# Nestling_2_1_EXB.net
KiCad netlist of a schematic drawn in Altium Designer
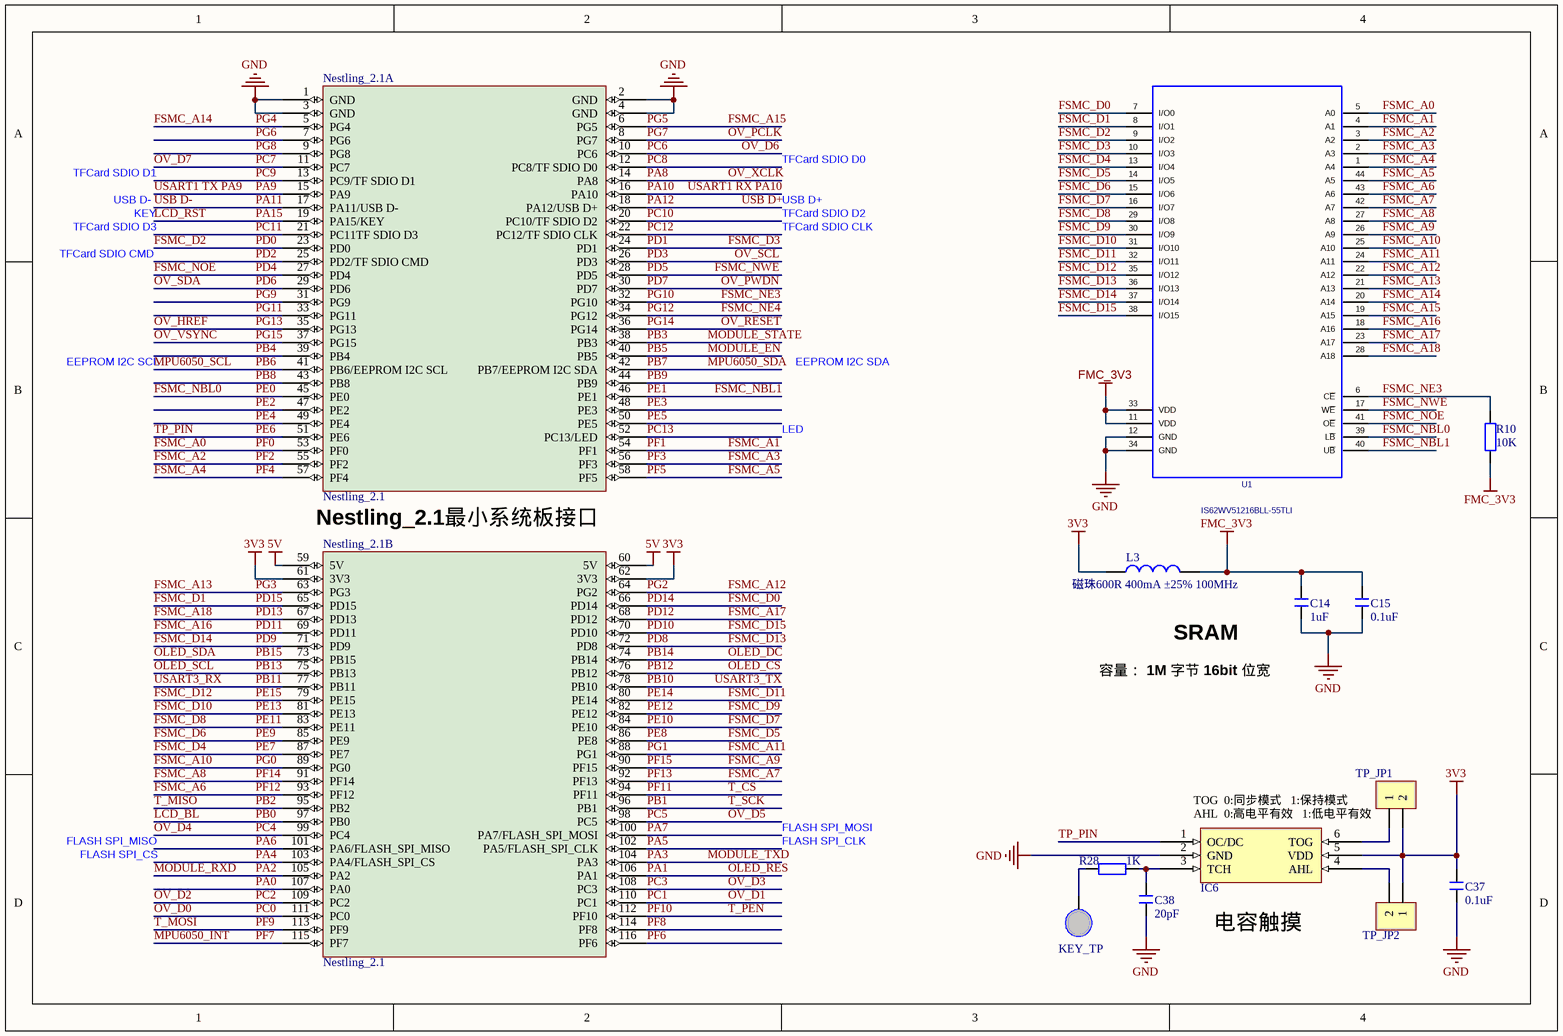
[diagram p0: Nestling_2.1_EXB.SchDoc]

(export (version "E")
  (design (tool "Eeschema 10.0.6"))
  (components
    (comp (ref "C14")
      (value "1uF")
      (footprint "C 0603_M")
      (description "无极性贴片电容")
      (fields (field (name "版权归属") "源创客"))
      (libsource (lib "altium-import") (part "root_1_C_"))
    )
    (comp (ref "C15")
      (value "0.1uF")
      (footprint "C 0603_M")
      (description "无极性贴片电容")
      (fields (field (name "版权归属") "源创客"))
      (libsource (lib "altium-import") (part "root_1_C_"))
    )
    (comp (ref "C37")
      (value "0.1uF")
      (footprint "C 0603_M")
      (description "无极性贴片电容")
      (fields (field (name "版权归属") "源创客"))
      (libsource (lib "altium-import") (part "root_1_C_"))
    )
    (comp (ref "C38")
      (value "20pF")
      (footprint "C 0603_M")
      (description "无极性贴片电容")
      (fields (field (name "版权归属") "源创客"))
      (libsource (lib "altium-import") (part "root_1_C_"))
    )
    (comp (ref "IC6")
      (value "RH6015C SOT23-6")
      (footprint "SOT23-6N")
      (description "贴片单通道电容式触摸感应控制开关IC")
      (libsource (lib "1.1   - IC芯片") (part "RH6015C"))
    )
    (comp (ref "KEY_TP")
      (value "TP_Pin")
      (footprint "TP_PIN_10*13mm")
      (libsource (lib "MyLib") (part "TP_Pin"))
    )
    (comp (ref "L3")
      (value "磁珠600R 400mA ±25% 100MHz")
      (footprint "L 0603")
      (description "小功率贴片电感")
      (fields (field (name "版权归属") "源创客"))
      (libsource (lib "altium-import") (part "root_0_L_"))
    )
    (comp (ref "Nestling_2.1")
      (value "Nestling_2.1")
      (footprint "Nestling_2.1")
      (libsource (lib "altium-import") (part "root_0_Nestling_2.1_"))
    )
    (comp (ref "R10")
      (value "10K")
      (footprint "R 0603_M")
      (description "Resistor")
      (libsource (lib "General") (part "RES"))
    )
    (comp (ref "R28")
      (value "1K")
      (footprint "R 0603_M")
      (description "Resistor")
      (libsource (lib "") (part "RES_1"))
    )
    (comp (ref "TP_JP1")
      (value "HDR-1X2")
      (footprint "HDR2.54-LI-2P")
      (description "2P接插件")
      (fields (field (name "版权归属") "源创客"))
      (libsource (lib "") (part "Header 2_1"))
    )
    (comp (ref "TP_JP2")
      (value "HDR-1X2")
      (footprint "HDR2.54-LI-2P")
      (description "2P接插件")
      (fields (field (name "版权归属") "源创客"))
      (libsource (lib "4.5   - 接插件-脚距2.54") (part "Header 2"))
    )
    (comp (ref "U1")
      (value "IS62WV51216BLL-55TLI")
      (footprint "TSOP44-0.8MM")
      (description "TSOP-II,2.5V - 3.6V, 512K x 16,55ns")
      (fields (field (name "TOLERANCE") "55ns"))
      (libsource (lib "altium-import") (part "root_0_IS62WV51216BLL-55TLI_"))
    )
  )
  (nets
    (net (code "1") (name "/FSMC_A0") (class "Default")
      (node (ref "Nestling_2.1") (pin "53") (pinfunction "PF0_53") (pintype "bidirectional"))
      (node (ref "U1") (pin "5") (pinfunction "A0_5") (pintype "passive"))
    )
    (net (code "2") (name "/FSMC_A1") (class "Default")
      (node (ref "Nestling_2.1") (pin "54") (pinfunction "PF1_54") (pintype "bidirectional"))
      (node (ref "U1") (pin "4") (pinfunction "A1_4") (pintype "passive"))
    )
    (net (code "3") (name "/FSMC_A2") (class "Default")
      (node (ref "Nestling_2.1") (pin "55") (pinfunction "PF2_55") (pintype "bidirectional"))
      (node (ref "U1") (pin "3") (pinfunction "A2_3") (pintype "passive"))
    )
    (net (code "4") (name "/FSMC_A3") (class "Default")
      (node (ref "Nestling_2.1") (pin "56") (pinfunction "PF3_56") (pintype "bidirectional"))
      (node (ref "U1") (pin "2") (pinfunction "A3_2") (pintype "passive"))
    )
    (net (code "5") (name "/FSMC_A4") (class "Default")
      (node (ref "Nestling_2.1") (pin "57") (pinfunction "PF4_57") (pintype "bidirectional"))
      (node (ref "U1") (pin "1") (pinfunction "A4_1") (pintype "passive"))
    )
    (net (code "6") (name "/FSMC_A5") (class "Default")
      (node (ref "Nestling_2.1") (pin "58") (pinfunction "PF5_58") (pintype "bidirectional"))
      (node (ref "U1") (pin "44") (pinfunction "A5_44") (pintype "passive"))
    )
    (net (code "7") (name "/FSMC_A6") (class "Default")
      (node (ref "Nestling_2.1") (pin "93") (pinfunction "PF12_93") (pintype "bidirectional"))
      (node (ref "U1") (pin "43") (pinfunction "A6_43") (pintype "passive"))
    )
    (net (code "8") (name "/FSMC_A7") (class "Default")
      (node (ref "Nestling_2.1") (pin "92") (pinfunction "PF13_92") (pintype "bidirectional"))
      (node (ref "U1") (pin "42") (pinfunction "A7_42") (pintype "passive"))
    )
    (net (code "9") (name "/FSMC_A8") (class "Default")
      (node (ref "Nestling_2.1") (pin "91") (pinfunction "PF14_91") (pintype "bidirectional"))
      (node (ref "U1") (pin "27") (pinfunction "A8_27") (pintype "passive"))
    )
    (net (code "10") (name "/FSMC_A9") (class "Default")
      (node (ref "Nestling_2.1") (pin "90") (pinfunction "PF15_90") (pintype "bidirectional"))
      (node (ref "U1") (pin "26") (pinfunction "A9_26") (pintype "passive"))
    )
    (net (code "11") (name "/FSMC_A10") (class "Default")
      (node (ref "Nestling_2.1") (pin "89") (pinfunction "PG0_89") (pintype "bidirectional"))
      (node (ref "U1") (pin "25") (pinfunction "A10_25") (pintype "passive"))
    )
    (net (code "12") (name "/FSMC_A11") (class "Default")
      (node (ref "Nestling_2.1") (pin "88") (pinfunction "PG1_88") (pintype "bidirectional"))
      (node (ref "U1") (pin "24") (pinfunction "A11_24") (pintype "passive"))
    )
    (net (code "13") (name "/FSMC_A12") (class "Default")
      (node (ref "Nestling_2.1") (pin "64") (pinfunction "PG2_64") (pintype "bidirectional"))
      (node (ref "U1") (pin "22") (pinfunction "A12_22") (pintype "passive"))
    )
    (net (code "14") (name "/FSMC_A13") (class "Default")
      (node (ref "Nestling_2.1") (pin "63") (pinfunction "PG3_63") (pintype "bidirectional"))
      (node (ref "U1") (pin "21") (pinfunction "A13_21") (pintype "passive"))
    )
    (net (code "15") (name "/FSMC_A14") (class "Default")
      (node (ref "Nestling_2.1") (pin "5") (pinfunction "PG4_5") (pintype "bidirectional"))
      (node (ref "U1") (pin "20") (pinfunction "A14_20") (pintype "passive"))
    )
    (net (code "16") (name "/FSMC_A15") (class "Default")
      (node (ref "Nestling_2.1") (pin "6") (pinfunction "PG5_6") (pintype "bidirectional"))
      (node (ref "U1") (pin "19") (pinfunction "A15_19") (pintype "passive"))
    )
    (net (code "17") (name "/FSMC_A16") (class "Default")
      (node (ref "Nestling_2.1") (pin "69") (pinfunction "PD11_69") (pintype "bidirectional"))
      (node (ref "U1") (pin "18") (pinfunction "A16_18") (pintype "passive"))
    )
    (net (code "18") (name "/FSMC_A17") (class "Default")
      (node (ref "Nestling_2.1") (pin "68") (pinfunction "PD12_68") (pintype "bidirectional"))
      (node (ref "U1") (pin "23") (pinfunction "A17_23") (pintype "passive"))
    )
    (net (code "19") (name "/FSMC_A18") (class "Default")
      (node (ref "Nestling_2.1") (pin "67") (pinfunction "PD13_67") (pintype "bidirectional"))
      (node (ref "U1") (pin "28") (pinfunction "A18_28") (pintype "passive"))
    )
    (net (code "20") (name "/FSMC_D0") (class "Default")
      (node (ref "Nestling_2.1") (pin "66") (pinfunction "PD14_66") (pintype "bidirectional"))
      (node (ref "U1") (pin "7") (pinfunction "I/O0_7") (pintype "passive"))
    )
    (net (code "21") (name "/FSMC_D1") (class "Default")
      (node (ref "Nestling_2.1") (pin "65") (pinfunction "PD15_65") (pintype "bidirectional"))
      (node (ref "U1") (pin "8") (pinfunction "I/O1_8") (pintype "passive"))
    )
    (net (code "22") (name "/FSMC_D2") (class "Default")
      (node (ref "Nestling_2.1") (pin "23") (pinfunction "PD0_23") (pintype "bidirectional"))
      (node (ref "U1") (pin "9") (pinfunction "I/O2_9") (pintype "passive"))
    )
    (net (code "23") (name "/FSMC_D3") (class "Default")
      (node (ref "Nestling_2.1") (pin "24") (pinfunction "PD1_24") (pintype "bidirectional"))
      (node (ref "U1") (pin "10") (pinfunction "I/O3_10") (pintype "passive"))
    )
    (net (code "24") (name "/FSMC_D4") (class "Default")
      (node (ref "Nestling_2.1") (pin "87") (pinfunction "PE7_87") (pintype "bidirectional"))
      (node (ref "U1") (pin "13") (pinfunction "I/O4_13") (pintype "passive"))
    )
    (net (code "25") (name "/FSMC_D5") (class "Default")
      (node (ref "Nestling_2.1") (pin "86") (pinfunction "PE8_86") (pintype "bidirectional"))
      (node (ref "U1") (pin "14") (pinfunction "I/O5_14") (pintype "passive"))
    )
    (net (code "26") (name "/FSMC_D6") (class "Default")
      (node (ref "Nestling_2.1") (pin "85") (pinfunction "PE9_85") (pintype "bidirectional"))
      (node (ref "U1") (pin "15") (pinfunction "I/O6_15") (pintype "passive"))
    )
    (net (code "27") (name "/FSMC_D7") (class "Default")
      (node (ref "Nestling_2.1") (pin "84") (pinfunction "PE10_84") (pintype "bidirectional"))
      (node (ref "U1") (pin "16") (pinfunction "I/O7_16") (pintype "passive"))
    )
    (net (code "28") (name "/FSMC_D8") (class "Default")
      (node (ref "Nestling_2.1") (pin "83") (pinfunction "PE11_83") (pintype "bidirectional"))
      (node (ref "U1") (pin "29") (pinfunction "I/O8_29") (pintype "passive"))
    )
    (net (code "29") (name "/FSMC_D9") (class "Default")
      (node (ref "Nestling_2.1") (pin "82") (pinfunction "PE12_82") (pintype "bidirectional"))
      (node (ref "U1") (pin "30") (pinfunction "I/O9_30") (pintype "passive"))
    )
    (net (code "30") (name "/FSMC_D10") (class "Default")
      (node (ref "Nestling_2.1") (pin "81") (pinfunction "PE13_81") (pintype "bidirectional"))
      (node (ref "U1") (pin "31") (pinfunction "I/O10_31") (pintype "passive"))
    )
    (net (code "31") (name "/FSMC_D11") (class "Default")
      (node (ref "Nestling_2.1") (pin "80") (pinfunction "PE14_80") (pintype "bidirectional"))
      (node (ref "U1") (pin "32") (pinfunction "I/O11_32") (pintype "passive"))
    )
    (net (code "32") (name "/FSMC_D12") (class "Default")
      (node (ref "Nestling_2.1") (pin "79") (pinfunction "PE15_79") (pintype "bidirectional"))
      (node (ref "U1") (pin "35") (pinfunction "I/O12_35") (pintype "passive"))
    )
    (net (code "33") (name "/FSMC_D13") (class "Default")
      (node (ref "Nestling_2.1") (pin "72") (pinfunction "PD8_72") (pintype "bidirectional"))
      (node (ref "U1") (pin "36") (pinfunction "I/O13_36") (pintype "passive"))
    )
    (net (code "34") (name "/FSMC_D14") (class "Default")
      (node (ref "Nestling_2.1") (pin "71") (pinfunction "PD9_71") (pintype "bidirectional"))
      (node (ref "U1") (pin "37") (pinfunction "I/O14_37") (pintype "passive"))
    )
    (net (code "35") (name "/FSMC_D15") (class "Default")
      (node (ref "Nestling_2.1") (pin "70") (pinfunction "PD10_70") (pintype "bidirectional"))
      (node (ref "U1") (pin "38") (pinfunction "I/O15_38") (pintype "passive"))
    )
    (net (code "36") (name "/FSMC_NBL0") (class "Default")
      (node (ref "Nestling_2.1") (pin "45") (pinfunction "PE0_45") (pintype "bidirectional"))
      (node (ref "U1") (pin "39") (pinfunction "L~{B}_39") (pintype "passive"))
    )
    (net (code "37") (name "/FSMC_NBL1") (class "Default")
      (node (ref "Nestling_2.1") (pin "46") (pinfunction "PE1_46") (pintype "bidirectional"))
      (node (ref "U1") (pin "40") (pinfunction "U~{B}_40") (pintype "passive"))
    )
    (net (code "38") (name "/FSMC_NE3") (class "Default")
      (node (ref "Nestling_2.1") (pin "32") (pinfunction "PG10_32") (pintype "bidirectional"))
      (node (ref "R10") (pin "1") (pinfunction "1_1") (pintype "passive"))
      (node (ref "U1") (pin "6") (pinfunction "C~{E}_6") (pintype "passive"))
    )
    (net (code "39") (name "/FSMC_NE4") (class "Default")
      (node (ref "Nestling_2.1") (pin "34") (pinfunction "PG12_34") (pintype "bidirectional"))
    )
    (net (code "40") (name "/FSMC_NOE") (class "Default")
      (node (ref "Nestling_2.1") (pin "27") (pinfunction "PD4_27") (pintype "bidirectional"))
      (node (ref "U1") (pin "41") (pinfunction "O~{E}_41") (pintype "passive"))
    )
    (net (code "41") (name "/FSMC_NWE") (class "Default")
      (node (ref "Nestling_2.1") (pin "28") (pinfunction "PD5_28") (pintype "bidirectional"))
      (node (ref "U1") (pin "17") (pinfunction "W~{E}_17") (pintype "passive"))
    )
    (net (code "42") (name "/LCD_BL") (class "Default")
      (node (ref "Nestling_2.1") (pin "97") (pinfunction "PB0_97") (pintype "bidirectional"))
    )
    (net (code "43") (name "/LCD_RST") (class "Default")
      (node (ref "Nestling_2.1") (pin "19") (pinfunction "PA15/KEY_19") (pintype "bidirectional"))
    )
    (net (code "44") (name "/MODULE_EN") (class "Default")
      (node (ref "Nestling_2.1") (pin "40") (pinfunction "PB5_40") (pintype "bidirectional"))
    )
    (net (code "45") (name "/MODULE_RXD") (class "Default")
      (node (ref "Nestling_2.1") (pin "105") (pinfunction "PA2_105") (pintype "bidirectional"))
    )
    (net (code "46") (name "/MODULE_STATE") (class "Default")
      (node (ref "Nestling_2.1") (pin "38") (pinfunction "PB3_38") (pintype "bidirectional"))
    )
    (net (code "47") (name "/MODULE_TXD") (class "Default")
      (node (ref "Nestling_2.1") (pin "104") (pinfunction "PA3_104") (pintype "bidirectional"))
    )
    (net (code "48") (name "/MPU6050_INT") (class "Default")
      (node (ref "Nestling_2.1") (pin "115") (pinfunction "PF7_115") (pintype "bidirectional"))
    )
    (net (code "49") (name "/MPU6050_SCL") (class "Default")
      (node (ref "Nestling_2.1") (pin "41") (pinfunction "PB6/EEPROM_I2C_SCL_41") (pintype "bidirectional"))
    )
    (net (code "50") (name "/MPU6050_SDA") (class "Default")
      (node (ref "Nestling_2.1") (pin "42") (pinfunction "PB7/EEPROM_I2C_SDA_42") (pintype "bidirectional"))
    )
    (net (code "51") (name "/OLED_CS") (class "Default")
      (node (ref "Nestling_2.1") (pin "76") (pinfunction "PB12_76") (pintype "bidirectional"))
    )
    (net (code "52") (name "/OLED_DC") (class "Default")
      (node (ref "Nestling_2.1") (pin "74") (pinfunction "PB14_74") (pintype "bidirectional"))
    )
    (net (code "53") (name "/OLED_RES") (class "Default")
      (node (ref "Nestling_2.1") (pin "106") (pinfunction "PA1_106") (pintype "bidirectional"))
    )
    (net (code "54") (name "/OLED_SCL") (class "Default")
      (node (ref "Nestling_2.1") (pin "75") (pinfunction "PB13_75") (pintype "bidirectional"))
    )
    (net (code "55") (name "/OLED_SDA") (class "Default")
      (node (ref "Nestling_2.1") (pin "73") (pinfunction "PB15_73") (pintype "bidirectional"))
    )
    (net (code "56") (name "/OV_D0") (class "Default")
      (node (ref "Nestling_2.1") (pin "111") (pinfunction "PC0_111") (pintype "bidirectional"))
    )
    (net (code "57") (name "/OV_D1") (class "Default")
      (node (ref "Nestling_2.1") (pin "110") (pinfunction "PC1_110") (pintype "bidirectional"))
    )
    (net (code "58") (name "/OV_D2") (class "Default")
      (node (ref "Nestling_2.1") (pin "109") (pinfunction "PC2_109") (pintype "bidirectional"))
    )
    (net (code "59") (name "/OV_D3") (class "Default")
      (node (ref "Nestling_2.1") (pin "108") (pinfunction "PC3_108") (pintype "bidirectional"))
    )
    (net (code "60") (name "/OV_D4") (class "Default")
      (node (ref "Nestling_2.1") (pin "99") (pinfunction "PC4_99") (pintype "bidirectional"))
    )
    (net (code "61") (name "/OV_D5") (class "Default")
      (node (ref "Nestling_2.1") (pin "98") (pinfunction "PC5_98") (pintype "bidirectional"))
    )
    (net (code "62") (name "/OV_D6") (class "Default")
      (node (ref "Nestling_2.1") (pin "10") (pinfunction "PC6_10") (pintype "bidirectional"))
    )
    (net (code "63") (name "/OV_D7") (class "Default")
      (node (ref "Nestling_2.1") (pin "11") (pinfunction "PC7_11") (pintype "bidirectional"))
    )
    (net (code "64") (name "/OV_HREF") (class "Default")
      (node (ref "Nestling_2.1") (pin "35") (pinfunction "PG13_35") (pintype "bidirectional"))
    )
    (net (code "65") (name "/OV_PCLK") (class "Default")
      (node (ref "Nestling_2.1") (pin "8") (pinfunction "PG7_8") (pintype "bidirectional"))
    )
    (net (code "66") (name "/OV_PWDN") (class "Default")
      (node (ref "Nestling_2.1") (pin "30") (pinfunction "PD7_30") (pintype "bidirectional"))
    )
    (net (code "67") (name "/OV_RESET") (class "Default")
      (node (ref "Nestling_2.1") (pin "36") (pinfunction "PG14_36") (pintype "bidirectional"))
    )
    (net (code "68") (name "/OV_SCL") (class "Default")
      (node (ref "Nestling_2.1") (pin "26") (pinfunction "PD3_26") (pintype "bidirectional"))
    )
    (net (code "69") (name "/OV_SDA") (class "Default")
      (node (ref "Nestling_2.1") (pin "29") (pinfunction "PD6_29") (pintype "bidirectional"))
    )
    (net (code "70") (name "/OV_VSYNC") (class "Default")
      (node (ref "Nestling_2.1") (pin "37") (pinfunction "PG15_37") (pintype "bidirectional"))
    )
    (net (code "71") (name "/OV_XCLK") (class "Default")
      (node (ref "Nestling_2.1") (pin "14") (pinfunction "PA8_14") (pintype "bidirectional"))
    )
    (net (code "72") (name "/PA0") (class "Default")
      (node (ref "Nestling_2.1") (pin "107") (pinfunction "PA0_107") (pintype "bidirectional"))
    )
    (net (code "73") (name "/PA4") (class "Default")
      (node (ref "Nestling_2.1") (pin "103") (pinfunction "PA4/FLASH_SPI_CS_103") (pintype "bidirectional"))
    )
    (net (code "74") (name "/PA5") (class "Default")
      (node (ref "Nestling_2.1") (pin "102") (pinfunction "PA5/FLASH_SPI_CLK_102") (pintype "bidirectional"))
    )
    (net (code "75") (name "/PA6") (class "Default")
      (node (ref "Nestling_2.1") (pin "101") (pinfunction "PA6/FLASH_SPI_MISO_101") (pintype "bidirectional"))
    )
    (net (code "76") (name "/PA7") (class "Default")
      (node (ref "Nestling_2.1") (pin "100") (pinfunction "PA7/FLASH_SPI_MOSI_100") (pintype "bidirectional"))
    )
    (net (code "77") (name "/PA9") (class "Default")
      (node (ref "Nestling_2.1") (pin "15") (pinfunction "PA9_15") (pintype "bidirectional"))
    )
    (net (code "78") (name "/PA10") (class "Default")
      (node (ref "Nestling_2.1") (pin "16") (pinfunction "PA10_16") (pintype "bidirectional"))
    )
    (net (code "79") (name "/PA11") (class "Default")
      (node (ref "Nestling_2.1") (pin "17") (pinfunction "PA11/USB_D-_17") (pintype "bidirectional"))
    )
    (net (code "80") (name "/PA12") (class "Default")
      (node (ref "Nestling_2.1") (pin "18") (pinfunction "PA12/USB_D+_18") (pintype "bidirectional"))
    )
    (net (code "81") (name "/PB1") (class "Default")
      (node (ref "Nestling_2.1") (pin "96") (pinfunction "PB1_96") (pintype "bidirectional"))
    )
    (net (code "82") (name "/PB2") (class "Default")
      (node (ref "Nestling_2.1") (pin "95") (pinfunction "PB2_95") (pintype "bidirectional"))
    )
    (net (code "83") (name "/PB4") (class "Default")
      (node (ref "Nestling_2.1") (pin "39") (pinfunction "PB4_39") (pintype "bidirectional"))
    )
    (net (code "84") (name "/PB8") (class "Default")
      (node (ref "Nestling_2.1") (pin "43") (pinfunction "PB8_43") (pintype "bidirectional"))
    )
    (net (code "85") (name "/PB9") (class "Default")
      (node (ref "Nestling_2.1") (pin "44") (pinfunction "PB9_44") (pintype "bidirectional"))
    )
    (net (code "86") (name "/PB10") (class "Default")
      (node (ref "Nestling_2.1") (pin "78") (pinfunction "PB10_78") (pintype "bidirectional"))
    )
    (net (code "87") (name "/PB11") (class "Default")
      (node (ref "Nestling_2.1") (pin "77") (pinfunction "PB11_77") (pintype "bidirectional"))
    )
    (net (code "88") (name "/PC8") (class "Default")
      (node (ref "Nestling_2.1") (pin "12") (pinfunction "PC8/TF_SDIO_D0_12") (pintype "bidirectional"))
    )
    (net (code "89") (name "/PC9") (class "Default")
      (node (ref "Nestling_2.1") (pin "13") (pinfunction "PC9/TF_SDIO_D1_13") (pintype "bidirectional"))
    )
    (net (code "90") (name "/PC10") (class "Default")
      (node (ref "Nestling_2.1") (pin "20") (pinfunction "PC10/TF_SDIO_D2_20") (pintype "bidirectional"))
    )
    (net (code "91") (name "/PC11") (class "Default")
      (node (ref "Nestling_2.1") (pin "21") (pinfunction "PC11TF_SDIO_D3_21") (pintype "bidirectional"))
    )
    (net (code "92") (name "/PC12") (class "Default")
      (node (ref "Nestling_2.1") (pin "22") (pinfunction "PC12/TF_SDIO_CLK_22") (pintype "bidirectional"))
    )
    (net (code "93") (name "/PC13") (class "Default")
      (node (ref "Nestling_2.1") (pin "52") (pinfunction "PC13/LED_52") (pintype "bidirectional"))
    )
    (net (code "94") (name "/PD2") (class "Default")
      (node (ref "Nestling_2.1") (pin "25") (pinfunction "PD2/TF_SDIO_CMD_25") (pintype "bidirectional"))
    )
    (net (code "95") (name "/PE2") (class "Default")
      (node (ref "Nestling_2.1") (pin "47") (pinfunction "PE2_47") (pintype "bidirectional"))
    )
    (net (code "96") (name "/PE3") (class "Default")
      (node (ref "Nestling_2.1") (pin "48") (pinfunction "PE3_48") (pintype "bidirectional"))
    )
    (net (code "97") (name "/PE4") (class "Default")
      (node (ref "Nestling_2.1") (pin "49") (pinfunction "PE4_49") (pintype "bidirectional"))
    )
    (net (code "98") (name "/PE5") (class "Default")
      (node (ref "Nestling_2.1") (pin "50") (pinfunction "PE5_50") (pintype "bidirectional"))
    )
    (net (code "99") (name "/PE6") (class "Default")
      (node (ref "IC6") (pin "1") (pinfunction "OC/DC_1") (pintype "input"))
      (node (ref "Nestling_2.1") (pin "51") (pinfunction "PE6_51") (pintype "bidirectional"))
    )
    (net (code "100") (name "/PF6") (class "Default")
      (node (ref "Nestling_2.1") (pin "116") (pinfunction "PF6_116") (pintype "bidirectional"))
    )
    (net (code "101") (name "/PF8") (class "Default")
      (node (ref "Nestling_2.1") (pin "114") (pinfunction "PF8_114") (pintype "bidirectional"))
    )
    (net (code "102") (name "/PF9") (class "Default")
      (node (ref "Nestling_2.1") (pin "113") (pinfunction "PF9_113") (pintype "bidirectional"))
    )
    (net (code "103") (name "/PF10") (class "Default")
      (node (ref "Nestling_2.1") (pin "112") (pinfunction "PF10_112") (pintype "bidirectional"))
    )
    (net (code "104") (name "/PF11") (class "Default")
      (node (ref "Nestling_2.1") (pin "94") (pinfunction "PF11_94") (pintype "bidirectional"))
    )
    (net (code "105") (name "/PG6") (class "Default")
      (node (ref "Nestling_2.1") (pin "7") (pinfunction "PG6_7") (pintype "bidirectional"))
    )
    (net (code "106") (name "/PG8") (class "Default")
      (node (ref "Nestling_2.1") (pin "9") (pinfunction "PG8_9") (pintype "bidirectional"))
    )
    (net (code "107") (name "/PG9") (class "Default")
      (node (ref "Nestling_2.1") (pin "31") (pinfunction "PG9_31") (pintype "bidirectional"))
    )
    (net (code "108") (name "/PG11") (class "Default")
      (node (ref "Nestling_2.1") (pin "33") (pinfunction "PG11_33") (pintype "bidirectional"))
    )
    (net (code "109") (name "3V3") (class "Default")
      (node (ref "C37") (pin "2") (pinfunction "2_2") (pintype "passive"))
      (node (ref "IC6") (pin "5") (pinfunction "VDD_5") (pintype "input"))
      (node (ref "L3") (pin "1") (pinfunction "1_1") (pintype "passive"))
      (node (ref "Nestling_2.1") (pin "61") (pinfunction "3V3_61") (pintype "bidirectional"))
      (node (ref "Nestling_2.1") (pin "62") (pinfunction "3V3_62") (pintype "bidirectional"))
      (node (ref "TP_JP1") (pin "2") (pinfunction "2_2") (pintype "passive"))
      (node (ref "TP_JP2") (pin "1") (pinfunction "1_1") (pintype "passive"))
    )
    (net (code "110") (name "5V") (class "Default")
      (node (ref "Nestling_2.1") (pin "59") (pinfunction "5V_59") (pintype "bidirectional"))
      (node (ref "Nestling_2.1") (pin "60") (pinfunction "5V_60") (pintype "bidirectional"))
    )
    (net (code "111") (name "FMC_3V3") (class "Default")
      (node (ref "C14") (pin "2") (pinfunction "2_2") (pintype "passive"))
      (node (ref "C15") (pin "2") (pinfunction "2_2") (pintype "passive"))
      (node (ref "L3") (pin "2") (pinfunction "2_2") (pintype "passive"))
      (node (ref "R10") (pin "2") (pinfunction "2_2") (pintype "passive"))
      (node (ref "U1") (pin "11") (pinfunction "VDD_11") (pintype "passive"))
      (node (ref "U1") (pin "33") (pinfunction "VDD_33") (pintype "passive"))
    )
    (net (code "112") (name "GND") (class "Default")
      (node (ref "C14") (pin "1") (pinfunction "1_1") (pintype "passive"))
      (node (ref "C15") (pin "1") (pinfunction "1_1") (pintype "passive"))
      (node (ref "C37") (pin "1") (pinfunction "1_1") (pintype "passive"))
      (node (ref "C38") (pin "1") (pinfunction "1_1") (pintype "passive"))
      (node (ref "IC6") (pin "2") (pinfunction "GND_2") (pintype "input"))
      (node (ref "Nestling_2.1") (pin "1") (pinfunction "GND_1") (pintype "bidirectional"))
      (node (ref "Nestling_2.1") (pin "2") (pinfunction "GND_2") (pintype "bidirectional"))
      (node (ref "Nestling_2.1") (pin "3") (pinfunction "GND_3") (pintype "bidirectional"))
      (node (ref "Nestling_2.1") (pin "4") (pinfunction "GND_4") (pintype "bidirectional"))
      (node (ref "U1") (pin "12") (pinfunction "GND_12") (pintype "passive"))
      (node (ref "U1") (pin "34") (pinfunction "GND_34") (pintype "passive"))
    )
    (net (code "113") (name "Net-(IC6-AHL)") (class "Default")
      (node (ref "IC6") (pin "4") (pinfunction "AHL_4") (pintype "input"))
      (node (ref "TP_JP2") (pin "2") (pinfunction "2_2") (pintype "passive"))
    )
    (net (code "114") (name "Net-(IC6-TCH)") (class "Default")
      (node (ref "C38") (pin "2") (pinfunction "2_2") (pintype "passive"))
      (node (ref "IC6") (pin "3") (pinfunction "TCH_3") (pintype "input"))
      (node (ref "R28") (pin "1") (pinfunction "1_1") (pintype "passive"))
    )
    (net (code "115") (name "Net-(IC6-TOG)") (class "Default")
      (node (ref "IC6") (pin "6") (pinfunction "TOG_6") (pintype "input"))
      (node (ref "TP_JP1") (pin "1") (pinfunction "1_1") (pintype "passive"))
    )
    (net (code "116") (name "Net-(KEY_TP-Pad1)") (class "Default")
      (node (ref "KEY_TP") (pin "1") (pinfunction "1_1") (pintype "passive"))
      (node (ref "R28") (pin "2") (pinfunction "2_2") (pintype "passive"))
    )
  )
)
